# Adafruit_Feather_M0_Basic_rev_C.net
KiCad netlist of a schematic drawn in Altium Designer
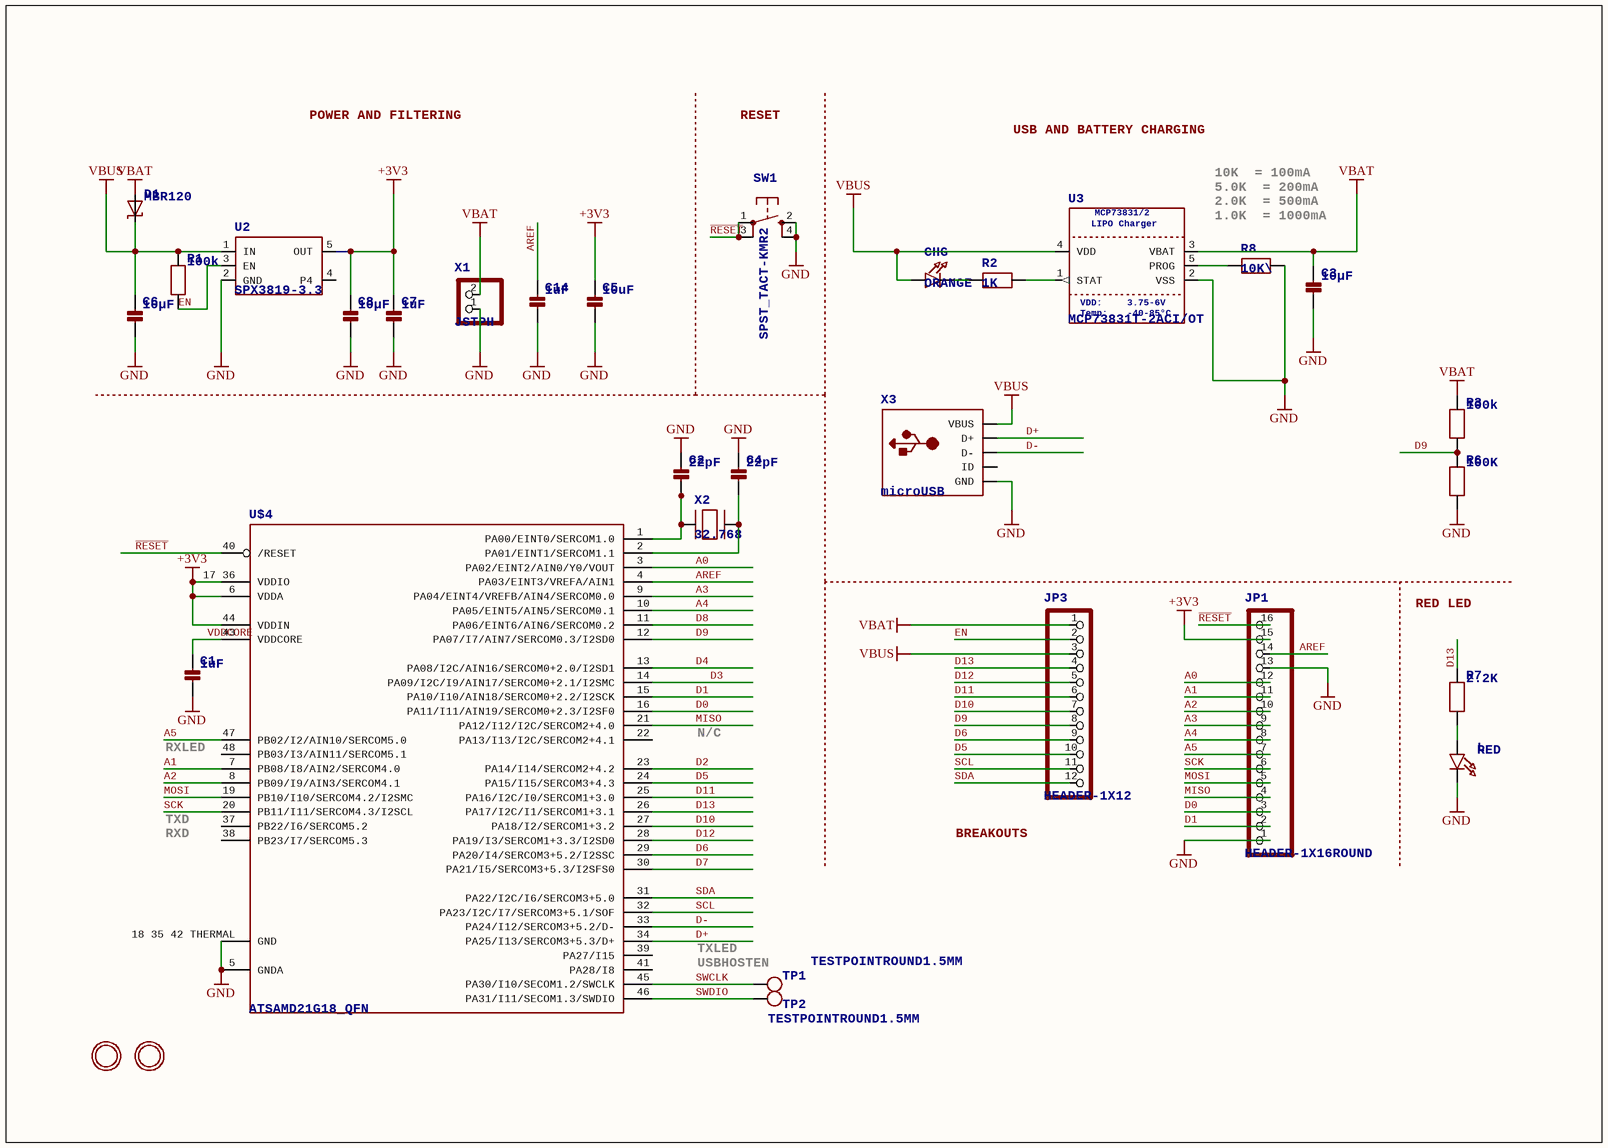
[diagram p0: Adafruit Feather M0 Basic rev C.SchDoc]

(export (version "E")
  (design (tool "Eeschema 10.0.6"))
  (components
    (comp (ref "C1")
      (value "1uF")
      (footprint "0603-NO")
      (fields (field (name "DRAWN") "KTOWN"))
      (libsource (lib "") (part "CAP_CERAMIC0603_NO_1"))
    )
    (comp (ref "C2")
      (value "22pF")
      (footprint "0603-NO")
      (fields (field (name "DRAWN") "KTOWN"))
      (libsource (lib "microbuilder") (part "CAP_CERAMIC0603_NO"))
    )
    (comp (ref "C3")
      (value "10µF")
      (footprint "0805-NO")
      (fields (field (name "DRAWN") "KTOWN"))
      (libsource (lib "microbuilder") (part "CAP_CERAMIC0805-NOOUTLINE"))
    )
    (comp (ref "C4")
      (value "22pF")
      (footprint "0603-NO")
      (fields (field (name "DRAWN") "KTOWN"))
      (libsource (lib "microbuilder") (part "CAP_CERAMIC0603_NO"))
    )
    (comp (ref "C5")
      (value "10uF")
      (footprint "0805-NO")
      (fields (field (name "DRAWN") "KTOWN"))
      (libsource (lib "microbuilder") (part "CAP_CERAMIC0805-NOOUTLINE"))
    )
    (comp (ref "C6")
      (value "10µF")
      (footprint "0805-NO")
      (fields (field (name "DRAWN") "KTOWN"))
      (libsource (lib "microbuilder") (part "CAP_CERAMIC0805-NOOUTLINE"))
    )
    (comp (ref "C7")
      (value "1uF")
      (footprint "0603-NO")
      (fields (field (name "DRAWN") "KTOWN"))
      (libsource (lib "") (part "CAP_CERAMIC0603_NO_1"))
    )
    (comp (ref "C8")
      (value "10µF")
      (footprint "0805-NO")
      (fields (field (name "DRAWN") "KTOWN"))
      (libsource (lib "microbuilder") (part "CAP_CERAMIC0805-NOOUTLINE"))
    )
    (comp (ref "C14")
      (value "1uF")
      (footprint "0603-NO")
      (fields (field (name "DRAWN") "KTOWN"))
      (libsource (lib "") (part "CAP_CERAMIC0603_NO_1"))
    )
    (comp (ref "CHG")
      (value "ORANGE")
      (footprint "CHIPLED_0805_NOOUTLINE")
      (fields (field (name "DRAWN") "KTOWN"))
      (libsource (lib "microbuilder") (part "LED0805_NOOUTLINE"))
    )
    (comp (ref "D1")
      (value "MBR120")
      (footprint "SOD-123")
      (fields (field (name "DRAWN") "KTOWN"))
      (libsource (lib "microbuilder") (part "DIODE-SCHOTTKYSOD-123"))
    )
    (comp (ref "JP1")
      (value "HEADER-1X16ROUND")
      (footprint "1X16_ROUND")
      (description "PIN HEADER")
      (fields (field (name "DRAWN") "KTOWN"))
      (libsource (lib "microbuilder") (part "HEADER-1X16ROUND"))
    )
    (comp (ref "JP3")
      (value "HEADER-1X12")
      (footprint "1X12_ROUND")
      (fields (field (name "DRAWN") "KTOWN"))
      (libsource (lib "microbuilder") (part "HEADER-1X12"))
    )
    (comp (ref "L")
      (value "RED")
      (footprint "CHIPLED_0805_NOOUTLINE")
      (fields (field (name "DRAWN") "KTOWN"))
      (libsource (lib "") (part "LED0805_NOOUTLINE_1"))
    )
    (comp (ref "R1")
      (value "100k")
      (footprint "0603-NO")
      (fields (field (name "DRAWN") "KTOWN"))
      (libsource (lib "microbuilder") (part "RESISTOR_0603_NOOUT"))
    )
    (comp (ref "R2")
      (value "1K")
      (footprint "0603-NO")
      (fields (field (name "DRAWN") "KTOWN"))
      (libsource (lib "microbuilder") (part "RESISTOR_0603_NOOUT"))
    )
    (comp (ref "R3")
      (value "100k")
      (footprint "0603-NO")
      (fields (field (name "DRAWN") "KTOWN"))
      (libsource (lib "microbuilder") (part "RESISTOR_0603_NOOUT"))
    )
    (comp (ref "R6")
      (value "100K")
      (footprint "0603-NO")
      (fields (field (name "DRAWN") "KTOWN"))
      (libsource (lib "microbuilder") (part "RESISTOR_0603_NOOUT"))
    )
    (comp (ref "R7")
      (value "2.2K")
      (footprint "0603-NO")
      (fields (field (name "DRAWN") "KTOWN"))
      (libsource (lib "microbuilder") (part "RESISTOR_0603_NOOUT"))
    )
    (comp (ref "R8")
      (value "10~{K}")
      (footprint "0603-NO")
      (fields (field (name "DRAWN") "KTOWN"))
      (libsource (lib "microbuilder") (part "RESISTOR_0603_NOOUT"))
    )
    (comp (ref "SW1")
      (value "SPST_TACT-KMR2")
      (footprint "KMR2")
      (description "SMT 6mm switch, EVQQ2 series    http://www.ladyada.net/library/eagle")
      (libsource (lib "adafruit") (part "SPST_TACT-KMR2"))
    )
    (comp (ref "TP1")
      (value "TESTPOINTROUND1.5MM")
      (footprint "TESTPOINT_ROUND_1.5MM")
      (fields (field (name "DRAWN") "KTOWN"))
      (libsource (lib "microbuilder") (part "TESTPOINTROUND1.5MM"))
    )
    (comp (ref "TP2")
      (value "TESTPOINTROUND1.5MM")
      (footprint "TESTPOINT_ROUND_1.5MM")
      (fields (field (name "DRAWN") "KTOWN"))
      (libsource (lib "microbuilder") (part "TESTPOINTROUND1.5MM"))
    )
    (comp (ref "U$4")
      (value "ATSAMD21G18_QFN")
      (footprint "TQFN48_7MM")
      (fields (field (name "DRAWN") "KTOWN"))
      (libsource (lib "microbuilder") (part "ATSAMD21J_QFN"))
    )
    (comp (ref "U$31")
      (value "MOUNTINGHOLE2.5")
      (footprint "MOUNTINGHOLE_2.5_PLATED")
      (description "Mounting Hole   For #2 screws (0.086\"/2.18mm width, 0.094\"/2.4mm hole) use 2.5mm")
      (fields (field (name "DRAWN") "KTOWN"))
      (libsource (lib "microbuilder") (part "MOUNTINGHOLE2.5"))
    )
    (comp (ref "U$32")
      (value "MOUNTINGHOLE2.5")
      (footprint "MOUNTINGHOLE_2.5_PLATED")
      (description "Mounting Hole   For #2 screws (0.086\"/2.18mm width, 0.094\"/2.4mm hole) use 2.5mm")
      (fields (field (name "DRAWN") "KTOWN"))
      (libsource (lib "microbuilder") (part "MOUNTINGHOLE2.5"))
    )
    (comp (ref "U2")
      (value "SPX3819-3.3")
      (footprint "SOT23-5")
      (fields (field (name "DRAWN") "KTOWN"))
      (libsource (lib "microbuilder") (part "VREG_SOT23-5"))
    )
    (comp (ref "U3")
      (value "MCP73831T-2ACI/OT")
      (footprint "SOT23-5")
      (fields
        (field (name "MCP73831/2") "MCP73831/2")
        (field (name "LIPOCHARGER") "LIPO Charger")
        (field (name "TEMP") "Temp:")
        (field (name "-40-85°C") "-40-85°C")
        (field (name "VDD") "VDD:")
        (field (name "3.75-6V") "3.75-6V")
        (field (name "DRAWN") "KTOWN")
      )
      (libsource (lib "microbuilder") (part "MCP73831/2"))
    )
    (comp (ref "X1")
      (value "JSTPH")
      (footprint "JSTPH2")
      (description "JST 2-Pin Right-Angle Connector  PH-Series - 4UConnector: 17311  SH-Series - 4UConnector: 07278")
      (fields (field (name "DRAWN") "KTOWN"))
      (libsource (lib "microbuilder") (part "CON_JST_PH_2PIN"))
    )
    (comp (ref "X2")
      (value "32.768")
      (footprint "XTAL3215")
      (description "Low cost SMT crystals, no capacitors included    http://www.ladyada.net/library/eagle")
      (fields (field (name "DRAWN") "KTOWN"))
      (libsource (lib "adafruit2") (part "XTAL-3.2X1.5"))
    )
    (comp (ref "X3")
      (value "microUSB")
      (footprint "4UCONN_20329_V2")
      (description "USB ConnectorsUSBMINIB - Surface Mount Female Mini-B USB Connector    4UConnector: 06564")
      (fields (field (name "DRAWN") "KTOWN"))
      (libsource (lib "microbuilder") (part "USB_MICRO_20329_V2"))
    )
  )
  (nets
    (net (code "1") (name "+3V3") (class "Default")
      (node (ref "C5") (pin "1") (pinfunction "1_1") (pintype "passive"))
      (node (ref "C7") (pin "1") (pinfunction "1_1") (pintype "passive"))
      (node (ref "C8") (pin "1") (pinfunction "1_1") (pintype "passive"))
      (node (ref "JP1") (pin "15") (pinfunction "15_15") (pintype "passive"))
      (node (ref "U$4") (pin "17_36") (pinfunction "VDDIO_17_36") (pintype "power_in"))
      (node (ref "U$4") (pin "44") (pinfunction "VDDIN_44") (pintype "power_in"))
      (node (ref "U$4") (pin "6") (pinfunction "VDDA_6") (pintype "power_in"))
      (node (ref "U2") (pin "5") (pinfunction "OUT_5") (pintype "open_emitter"))
    )
    (net (code "2") (name "/A0") (class "Default")
      (node (ref "JP1") (pin "12") (pinfunction "12_12") (pintype "passive"))
      (node (ref "U$4") (pin "3") (pinfunction "PA02/EINT2/AIN0/Y0/VOUT_3") (pintype "passive"))
    )
    (net (code "3") (name "/A1") (class "Default")
      (node (ref "JP1") (pin "11") (pinfunction "11_11") (pintype "passive"))
      (node (ref "U$4") (pin "7") (pinfunction "PB08/I8/AIN2/SERCOM4.0_7") (pintype "passive"))
    )
    (net (code "4") (name "/A2") (class "Default")
      (node (ref "JP1") (pin "10") (pinfunction "10_10") (pintype "passive"))
      (node (ref "U$4") (pin "8") (pinfunction "PB09/I9/AIN3/SERCOM4.1_8") (pintype "passive"))
    )
    (net (code "5") (name "/A3") (class "Default")
      (node (ref "JP1") (pin "9") (pinfunction "9_9") (pintype "passive"))
      (node (ref "U$4") (pin "9") (pinfunction "PA04/EINT4/VREFB/AIN4/SERCOM0.0_9") (pintype "passive"))
    )
    (net (code "6") (name "/A4") (class "Default")
      (node (ref "JP1") (pin "8") (pinfunction "8_8") (pintype "passive"))
      (node (ref "U$4") (pin "10") (pinfunction "PA05/EINT5/AIN5/SERCOM0.1_10") (pintype "passive"))
    )
    (net (code "7") (name "/A5") (class "Default")
      (node (ref "JP1") (pin "7") (pinfunction "7_7") (pintype "passive"))
      (node (ref "U$4") (pin "47") (pinfunction "PB02/I2/AIN10/SERCOM5.0_47") (pintype "passive"))
    )
    (net (code "8") (name "/AREF") (class "Default")
      (node (ref "C14") (pin "1") (pinfunction "1_1") (pintype "passive"))
      (node (ref "JP1") (pin "14") (pinfunction "14_14") (pintype "passive"))
      (node (ref "U$4") (pin "4") (pinfunction "PA03/EINT3/VREFA/AIN1_4") (pintype "passive"))
    )
    (net (code "9") (name "/D+") (class "Default")
      (node (ref "U$4") (pin "34") (pinfunction "PA25/I13/SERCOM3+5.3/D+_34") (pintype "passive"))
      (node (ref "X3") (pin "D+") (pinfunction "D+_D+") (pintype "passive"))
    )
    (net (code "10") (name "/D-") (class "Default")
      (node (ref "U$4") (pin "33") (pinfunction "PA24/I12/SERCOM3+5.2/D-_33") (pintype "passive"))
      (node (ref "X3") (pin "D-") (pinfunction "D-_D-") (pintype "passive"))
    )
    (net (code "11") (name "/D0") (class "Default")
      (node (ref "JP1") (pin "3") (pinfunction "3_3") (pintype "passive"))
      (node (ref "U$4") (pin "16") (pinfunction "PA11/I11/AIN19/SERCOM0+2.3/I2SF0_16") (pintype "passive"))
    )
    (net (code "12") (name "/D1") (class "Default")
      (node (ref "JP1") (pin "2") (pinfunction "2_2") (pintype "passive"))
      (node (ref "U$4") (pin "15") (pinfunction "PA10/I10/AIN18/SERCOM0+2.2/I2SCK_15") (pintype "passive"))
    )
    (net (code "13") (name "/D2") (class "Default")
      (node (ref "U$4") (pin "23") (pinfunction "PA14/I14/SERCOM2+4.2_23") (pintype "passive"))
    )
    (net (code "14") (name "/D3") (class "Default")
      (node (ref "U$4") (pin "14") (pinfunction "PA09/I2C/I9/AIN17/SERCOM0+2.1/I2SMC_14") (pintype "passive"))
    )
    (net (code "15") (name "/D4") (class "Default")
      (node (ref "U$4") (pin "13") (pinfunction "PA08/I2C/AIN16/SERCOM0+2.0/I2SD1_13") (pintype "passive"))
    )
    (net (code "16") (name "/D5") (class "Default")
      (node (ref "JP3") (pin "10") (pinfunction "10_10") (pintype "passive"))
      (node (ref "U$4") (pin "24") (pinfunction "PA15/I15/SERCOM3+4.3_24") (pintype "passive"))
    )
    (net (code "17") (name "/D6") (class "Default")
      (node (ref "JP3") (pin "9") (pinfunction "9_9") (pintype "passive"))
      (node (ref "U$4") (pin "29") (pinfunction "PA20/I4/SERCOM3+5.2/I2SSC_29") (pintype "passive"))
    )
    (net (code "18") (name "/D7") (class "Default")
      (node (ref "U$4") (pin "30") (pinfunction "PA21/I5/SERCOM3+5.3/I2SFS0_30") (pintype "passive"))
    )
    (net (code "19") (name "/D8") (class "Default")
      (node (ref "U$4") (pin "11") (pinfunction "PA06/EINT6/AIN6/SERCOM0.2_11") (pintype "passive"))
    )
    (net (code "20") (name "/D9") (class "Default")
      (node (ref "JP3") (pin "8") (pinfunction "8_8") (pintype "passive"))
      (node (ref "R3") (pin "2") (pinfunction "2_2") (pintype "passive"))
      (node (ref "R6") (pin "1") (pinfunction "1_1") (pintype "passive"))
      (node (ref "U$4") (pin "12") (pinfunction "PA07/I7/AIN7/SERCOM0.3/I2SD0_12") (pintype "passive"))
    )
    (net (code "21") (name "/D10") (class "Default")
      (node (ref "JP3") (pin "7") (pinfunction "7_7") (pintype "passive"))
      (node (ref "U$4") (pin "27") (pinfunction "PA18/I2/SERCOM1+3.2_27") (pintype "passive"))
    )
    (net (code "22") (name "/D11") (class "Default")
      (node (ref "JP3") (pin "6") (pinfunction "6_6") (pintype "passive"))
      (node (ref "U$4") (pin "25") (pinfunction "PA16/I2C/I0/SERCOM1+3.0_25") (pintype "passive"))
    )
    (net (code "23") (name "/D12") (class "Default")
      (node (ref "JP3") (pin "5") (pinfunction "5_5") (pintype "passive"))
      (node (ref "U$4") (pin "28") (pinfunction "PA19/I3/SERCOM1+3.3/I2SD0_28") (pintype "passive"))
    )
    (net (code "24") (name "/D13") (class "Default")
      (node (ref "JP3") (pin "4") (pinfunction "4_4") (pintype "passive"))
      (node (ref "R7") (pin "1") (pinfunction "1_1") (pintype "passive"))
      (node (ref "U$4") (pin "26") (pinfunction "PA17/I2C/I1/SERCOM1+3.1_26") (pintype "passive"))
    )
    (net (code "25") (name "/EN") (class "Default")
      (node (ref "JP3") (pin "2") (pinfunction "2_2") (pintype "passive"))
      (node (ref "R1") (pin "2") (pinfunction "2_2") (pintype "passive"))
      (node (ref "U2") (pin "3") (pinfunction "EN_3") (pintype "passive"))
    )
    (net (code "26") (name "/MISO") (class "Default")
      (node (ref "JP1") (pin "4") (pinfunction "4_4") (pintype "passive"))
      (node (ref "U$4") (pin "21") (pinfunction "PA12/I12/I2C/SERCOM2+4.0_21") (pintype "passive"))
    )
    (net (code "27") (name "/MOSI") (class "Default")
      (node (ref "JP1") (pin "5") (pinfunction "5_5") (pintype "passive"))
      (node (ref "U$4") (pin "19") (pinfunction "PB10/I10/SERCOM4.2/I2SMC_19") (pintype "passive"))
    )
    (net (code "28") (name "/SCK") (class "Default")
      (node (ref "JP1") (pin "6") (pinfunction "6_6") (pintype "passive"))
      (node (ref "U$4") (pin "20") (pinfunction "PB11/I11/SERCOM4.3/I2SCL_20") (pintype "passive"))
    )
    (net (code "29") (name "/SCL") (class "Default")
      (node (ref "JP3") (pin "11") (pinfunction "11_11") (pintype "passive"))
      (node (ref "U$4") (pin "32") (pinfunction "PA23/I2C/I7/SERCOM3+5.1/SOF_32") (pintype "passive"))
    )
    (net (code "30") (name "/SDA") (class "Default")
      (node (ref "JP3") (pin "12") (pinfunction "12_12") (pintype "passive"))
      (node (ref "U$4") (pin "31") (pinfunction "PA22/I2C/I6/SERCOM3+5.0_31") (pintype "passive"))
    )
    (net (code "31") (name "/SWCLK") (class "Default")
      (node (ref "TP1") (pin "P$1") (pinfunction "P$1_P$1") (pintype "passive"))
      (node (ref "U$4") (pin "45") (pinfunction "PA30/I10/SECOM1.2/SWCLK_45") (pintype "passive"))
    )
    (net (code "32") (name "/SWDIO") (class "Default")
      (node (ref "TP2") (pin "P$1") (pinfunction "P$1_P$1") (pintype "passive"))
      (node (ref "U$4") (pin "46") (pinfunction "PA31/I11/SECOM1.3/SWDIO_46") (pintype "passive"))
    )
    (net (code "33") (name "/VDDCORE") (class "Default")
      (node (ref "C1") (pin "1") (pinfunction "1_1") (pintype "passive"))
      (node (ref "U$4") (pin "43") (pinfunction "VDDCORE_43") (pintype "power_in"))
    )
    (net (code "34") (name "/~{RESET}") (class "Default")
      (node (ref "JP1") (pin "16") (pinfunction "16_16") (pintype "passive"))
      (node (ref "SW1") (pin "1") (pinfunction "P_1") (pintype "passive"))
      (node (ref "SW1") (pin "3") (pinfunction "P1_3") (pintype "passive"))
      (node (ref "U$4") (pin "40") (pinfunction "/RESET_40") (pintype "passive"))
    )
    (net (code "35") (name "GND") (class "Default")
      (node (ref "C1") (pin "2") (pinfunction "2_2") (pintype "passive"))
      (node (ref "C14") (pin "2") (pinfunction "2_2") (pintype "passive"))
      (node (ref "C2") (pin "2") (pinfunction "2_2") (pintype "passive"))
      (node (ref "C3") (pin "2") (pinfunction "2_2") (pintype "passive"))
      (node (ref "C4") (pin "2") (pinfunction "2_2") (pintype "passive"))
      (node (ref "C5") (pin "2") (pinfunction "2_2") (pintype "passive"))
      (node (ref "C6") (pin "2") (pinfunction "2_2") (pintype "passive"))
      (node (ref "C7") (pin "2") (pinfunction "2_2") (pintype "passive"))
      (node (ref "C8") (pin "2") (pinfunction "2_2") (pintype "passive"))
      (node (ref "JP1") (pin "1") (pinfunction "1_1") (pintype "passive"))
      (node (ref "JP1") (pin "13") (pinfunction "13_13") (pintype "passive"))
      (node (ref "L") (pin "C") (pinfunction "C_C") (pintype "passive"))
      (node (ref "R6") (pin "2") (pinfunction "2_2") (pintype "passive"))
      (node (ref "R8") (pin "2") (pinfunction "2_2") (pintype "passive"))
      (node (ref "SW1") (pin "2") (pinfunction "S_2") (pintype "passive"))
      (node (ref "SW1") (pin "4") (pinfunction "S1_4") (pintype "passive"))
      (node (ref "U$4") (pin "18_35_42_THERMAL") (pinfunction "GND_18_35_42_THERMAL") (pintype "power_in"))
      (node (ref "U$4") (pin "5") (pinfunction "GNDA_5") (pintype "power_in"))
      (node (ref "U2") (pin "2") (pinfunction "GND_2") (pintype "power_in"))
      (node (ref "U3") (pin "2") (pinfunction "VSS_2") (pintype "power_in"))
      (node (ref "X1") (pin "1") (pinfunction "1_1") (pintype "passive"))
      (node (ref "X3") (pin "BASE@1_BASE@2_GND_SPRT@1_SPRT@2_SPRT@3_SPRT@4") (pinfunction "GND_BASE@1_BASE@2_GND_SPRT@1_SPRT@2_SPRT@3_SPRT@4") (pintype "power_in"))
    )
    (net (code "36") (name "Net-(CHG-PadC)") (class "Default")
      (node (ref "CHG") (pin "C") (pinfunction "C_C") (pintype "passive"))
      (node (ref "R2") (pin "1") (pinfunction "1_1") (pintype "passive"))
    )
    (net (code "37") (name "Net-(L-PadA)") (class "Default")
      (node (ref "L") (pin "A") (pinfunction "A_A") (pintype "passive"))
      (node (ref "R7") (pin "2") (pinfunction "2_2") (pintype "passive"))
    )
    (net (code "38") (name "Net-(U$4-PA00{slash}EINT0{slash}SERCOM1.0)") (class "Default")
      (node (ref "C2") (pin "1") (pinfunction "1_1") (pintype "passive"))
      (node (ref "U$4") (pin "1") (pinfunction "PA00/EINT0/SERCOM1.0_1") (pintype "passive"))
      (node (ref "X2") (pin "P$1") (pinfunction "P$1_P$1") (pintype "passive"))
    )
    (net (code "39") (name "Net-(U$4-PA01{slash}EINT1{slash}SERCOM1.1)") (class "Default")
      (node (ref "C4") (pin "1") (pinfunction "1_1") (pintype "passive"))
      (node (ref "U$4") (pin "2") (pinfunction "PA01/EINT1/SERCOM1.1_2") (pintype "passive"))
      (node (ref "X2") (pin "P$2") (pinfunction "P$2_P$2") (pintype "passive"))
    )
    (net (code "40") (name "Net-(U3-PROG)") (class "Default")
      (node (ref "R8") (pin "1") (pinfunction "1_1") (pintype "passive"))
      (node (ref "U3") (pin "5") (pinfunction "PROG_5") (pintype "passive"))
    )
    (net (code "41") (name "Net-(U3-STAT)") (class "Default")
      (node (ref "R2") (pin "2") (pinfunction "2_2") (pintype "passive"))
      (node (ref "U3") (pin "1") (pinfunction "STAT_1") (pintype "output"))
    )
    (net (code "42") (name "VBAT") (class "Default")
      (node (ref "C3") (pin "1") (pinfunction "1_1") (pintype "passive"))
      (node (ref "D1") (pin "A") (pinfunction "A_A") (pintype "passive"))
      (node (ref "JP3") (pin "1") (pinfunction "1_1") (pintype "passive"))
      (node (ref "R3") (pin "1") (pinfunction "1_1") (pintype "passive"))
      (node (ref "U3") (pin "3") (pinfunction "VBAT_3") (pintype "power_in"))
      (node (ref "X1") (pin "2") (pinfunction "2_2") (pintype "passive"))
    )
    (net (code "43") (name "VBUS") (class "Default")
      (node (ref "C6") (pin "1") (pinfunction "1_1") (pintype "passive"))
      (node (ref "CHG") (pin "A") (pinfunction "A_A") (pintype "passive"))
      (node (ref "D1") (pin "C") (pinfunction "C_C") (pintype "passive"))
      (node (ref "JP3") (pin "3") (pinfunction "3_3") (pintype "passive"))
      (node (ref "R1") (pin "1") (pinfunction "1_1") (pintype "passive"))
      (node (ref "U2") (pin "1") (pinfunction "IN_1") (pintype "power_in"))
      (node (ref "U3") (pin "4") (pinfunction "VDD_4") (pintype "power_in"))
      (node (ref "X3") (pin "VBUS") (pinfunction "VBUS_VBUS") (pintype "power_in"))
    )
    (net (code "44") (name "unconnected-(U$4-PA13{slash}I13{slash}I2C{slash}SERCOM2+4.1-Pad22)") (class "Default")
      (node (ref "U$4") (pin "22") (pinfunction "PA13/I13/I2C/SERCOM2+4.1_22") (pintype "passive"))
    )
    (net (code "45") (name "unconnected-(U$4-PA27{slash}I15-Pad39)") (class "Default")
      (node (ref "U$4") (pin "39") (pinfunction "PA27/I15_39") (pintype "passive"))
    )
    (net (code "46") (name "unconnected-(U$4-PA28{slash}I8-Pad41)") (class "Default")
      (node (ref "U$4") (pin "41") (pinfunction "PA28/I8_41") (pintype "passive"))
    )
    (net (code "47") (name "unconnected-(U$4-PB03{slash}I3{slash}AIN11{slash}SERCOM5.1-Pad48)") (class "Default")
      (node (ref "U$4") (pin "48") (pinfunction "PB03/I3/AIN11/SERCOM5.1_48") (pintype "passive"))
    )
    (net (code "48") (name "unconnected-(U$4-PB22{slash}I6{slash}SERCOM5.2-Pad37)") (class "Default")
      (node (ref "U$4") (pin "37") (pinfunction "PB22/I6/SERCOM5.2_37") (pintype "passive"))
    )
    (net (code "49") (name "unconnected-(U$4-PB23{slash}I7{slash}SERCOM5.3-Pad38)") (class "Default")
      (node (ref "U$4") (pin "38") (pinfunction "PB23/I7/SERCOM5.3_38") (pintype "passive"))
    )
    (net (code "50") (name "unconnected-(U2-P4-Pad4)") (class "Default")
      (node (ref "U2") (pin "4") (pinfunction "P4_4") (pintype "passive"))
    )
    (net (code "51") (name "unconnected-(X3-PadID)") (class "Default")
      (node (ref "X3") (pin "ID") (pinfunction "ID_ID") (pintype "passive"))
    )
  )
)
